# RainbowLED_2021_04_08_A.net
KiCad netlist of a schematic drawn in EAGLE
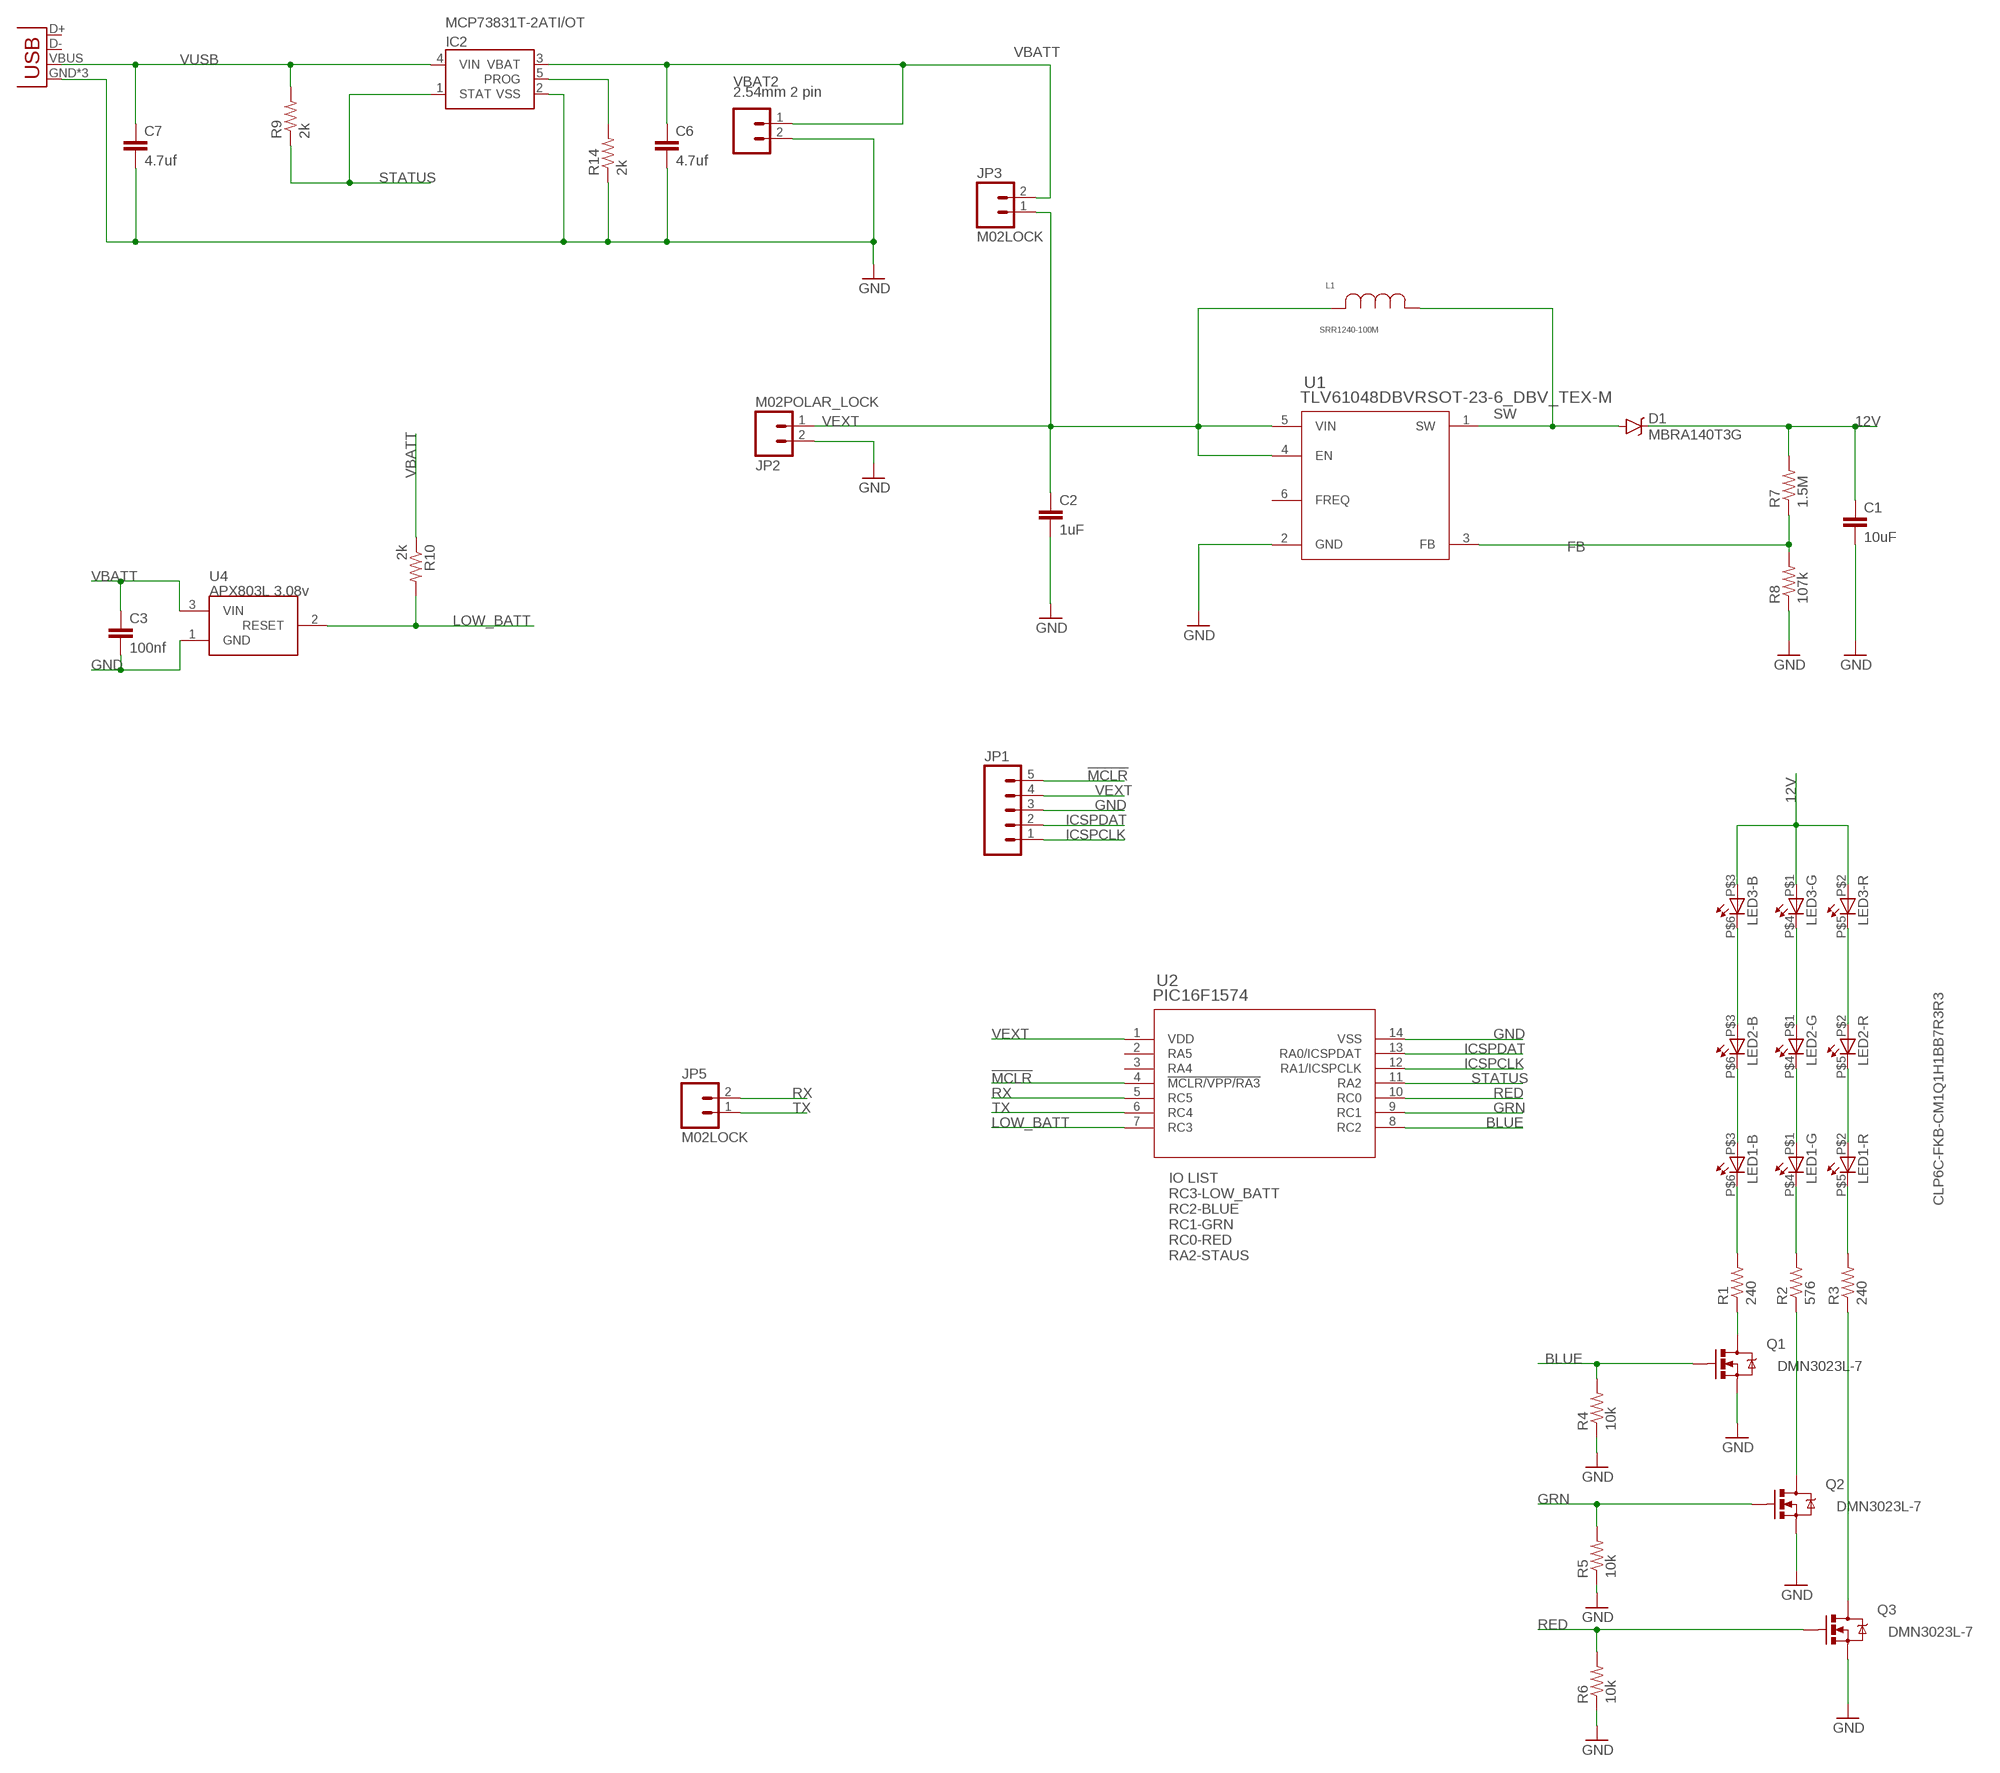
[diagram p0: schematic, sheet 1]

(export (version "E")
  (design (tool "Eeschema 10.0.6"))
  (components
    (comp (ref "C1")
      (value "10uF")
      (footprint "eagle-import:1206")
      (libsource (lib "eagle-import") (part "CAP1206"))
    )
    (comp (ref "C2")
      (value "1uF")
      (footprint "eagle-import:1206")
      (libsource (lib "eagle-import") (part "CAP1206"))
    )
    (comp (ref "C3")
      (value "100nf")
      (footprint "eagle-import:1206")
      (libsource (lib "eagle-import") (part "CAP1206"))
    )
    (comp (ref "C6")
      (value "4.7uf")
      (footprint "eagle-import:1206")
      (libsource (lib "eagle-import") (part "CAP1206"))
    )
    (comp (ref "C7")
      (value "4.7uf")
      (footprint "eagle-import:1206")
      (libsource (lib "eagle-import") (part "CAP1206"))
    )
    (comp (ref "D1")
      (value "MBRA140T3G")
      (footprint "eagle-import:SMA-DIODE")
      (libsource (lib "eagle-import") (part "DIODE-SCHOTTKY-MBRA140"))
    )
    (comp (ref "IC2")
      (value "MCP73831T-2ATI/OT")
      (footprint "eagle-import:SOT23-5")
      (libsource (lib "eagle-import") (part "MCP73831"))
    )
    (comp (ref "JP1")
      (value "M05LOCK")
      (footprint "eagle-import:1X05_LOCK")
      (libsource (lib "eagle-import") (part "M05LOCK"))
    )
    (comp (ref "JP2")
      (value "M02POLAR_LOCK")
      (footprint "eagle-import:MOLEX-1X2_LOCK")
      (libsource (lib "eagle-import") (part "M02POLAR_LOCK"))
    )
    (comp (ref "JP3")
      (value "M02LOCK")
      (footprint "eagle-import:1X02_LOCK")
      (libsource (lib "eagle-import") (part "M02LOCK"))
    )
    (comp (ref "JP4")
      (value "USB-MICROB")
      (footprint "eagle-import:USB-MICROB")
      (libsource (lib "eagle-import") (part "USB-MICROB"))
    )
    (comp (ref "JP5")
      (value "M02LOCK")
      (footprint "eagle-import:1X02_LOCK")
      (libsource (lib "eagle-import") (part "M02LOCK"))
    )
    (comp (ref "L1")
      (value "SRR1240-100M")
      (footprint "eagle-import:IND_BOURNS_SRR1240")
      (fields (field (name "MANUFACTURER_PART_NUMBER") "SRR1240100M"))
      (libsource (lib "eagle-import") (part "SRR1240-100M"))
    )
    (comp (ref "LED1")
      (value "CLX6F-FKC-CKNNQDGBB7A363")
      (footprint "eagle-import:PLCC-6")
      (libsource (lib "eagle-import") (part "OVSTRGBBCR8"))
    )
    (comp (ref "LED2")
      (value "CLX6F-FKC-CKNNQDGBB7A363")
      (footprint "eagle-import:PLCC-6")
      (libsource (lib "eagle-import") (part "OVSTRGBBCR8"))
    )
    (comp (ref "LED3")
      (value "CLX6F-FKC-CKNNQDGBB7A363")
      (footprint "eagle-import:PLCC-6")
      (libsource (lib "eagle-import") (part "OVSTRGBBCR8"))
    )
    (comp (ref "Q1")
      (value "DMN3023L-7")
      (footprint "eagle-import:SOT23-3")
      (libsource (lib "eagle-import") (part "MOSFET-NCHANNELBSS138"))
    )
    (comp (ref "Q2")
      (value "DMN3023L-7")
      (footprint "eagle-import:SOT23-3")
      (libsource (lib "eagle-import") (part "MOSFET-NCHANNELBSS138"))
    )
    (comp (ref "Q3")
      (value "DMN3023L-7")
      (footprint "eagle-import:SOT23-3")
      (libsource (lib "eagle-import") (part "MOSFET-NCHANNELBSS138"))
    )
    (comp (ref "R1")
      (value "240")
      (footprint "eagle-import:1206")
      (libsource (lib "eagle-import") (part "RESISTOR1206"))
    )
    (comp (ref "R2")
      (value "576")
      (footprint "eagle-import:1206")
      (libsource (lib "eagle-import") (part "RESISTOR1206"))
    )
    (comp (ref "R3")
      (value "240")
      (footprint "eagle-import:1206")
      (libsource (lib "eagle-import") (part "RESISTOR1206"))
    )
    (comp (ref "R4")
      (value "10k")
      (footprint "eagle-import:1206")
      (libsource (lib "eagle-import") (part "RESISTOR1206"))
    )
    (comp (ref "R5")
      (value "10k")
      (footprint "eagle-import:1206")
      (libsource (lib "eagle-import") (part "RESISTOR1206"))
    )
    (comp (ref "R6")
      (value "10k")
      (footprint "eagle-import:1206")
      (libsource (lib "eagle-import") (part "RESISTOR1206"))
    )
    (comp (ref "R7")
      (value "1.5M")
      (footprint "eagle-import:1206")
      (libsource (lib "eagle-import") (part "RESISTOR1206"))
    )
    (comp (ref "R8")
      (value "107k")
      (footprint "eagle-import:1206")
      (libsource (lib "eagle-import") (part "RESISTOR1206"))
    )
    (comp (ref "R9")
      (value "2k")
      (footprint "eagle-import:1206")
      (libsource (lib "eagle-import") (part "SparkFun-Resistors_RESISTOR1206"))
    )
    (comp (ref "R10")
      (value "2k")
      (footprint "eagle-import:1206")
      (libsource (lib "eagle-import") (part "SparkFun-Resistors_RESISTOR1206"))
    )
    (comp (ref "R14")
      (value "2k")
      (footprint "eagle-import:1206")
      (libsource (lib "eagle-import") (part "SparkFun-Resistors_RESISTOR1206"))
    )
    (comp (ref "U1")
      (value "TLV61048DBVRSOT-23-6_DBV_TEX-M")
      (footprint "eagle-import:SOT-23-6_DBV_TEX-M")
      (fields
        (field (name "MANUFACTURER_PART_NUMBER") "TLV61048DBVR")
        (field (name "COPYRIGHT") "Copyright (C) 2018 Accelerated Designs. All rights reserved")
      )
      (libsource (lib "eagle-import") (part "TLV61048DBVRSOT-23-6_DBV_TEX-M"))
    )
    (comp (ref "U2")
      (value "PIC16F1574")
      (footprint "eagle-import:SOIC14_SL")
      (fields (field (name "MANUFACTURER_PART_NUMBER") "PIC16F1503-I/SL"))
      (libsource (lib "eagle-import") (part "PIC16F1503-I/SL"))
    )
    (comp (ref "U4")
      (value "APX803L 3.08v")
      (footprint "eagle-import:SOT23")
      (libsource (lib "eagle-import") (part "ADP160"))
    )
    (comp (ref "VBAT2")
      (value "2.54mm 2 pin")
      (footprint "eagle-import:JST-2-PTH-VERT")
      (libsource (lib "eagle-import") (part "M02JST-PTH-VERT"))
    )
  )
  (nets
    (net (code "1") (name "/12V") (class "Default")
      (node (ref "C1") (pin "1") (pinfunction "1_1") (pintype "passive"))
      (node (ref "D1") (pin "C") (pinfunction "C_C") (pintype "passive"))
      (node (ref "LED3") (pin "P$1") (pinfunction "A_P$1") (pintype "passive"))
      (node (ref "LED3") (pin "P$2") (pinfunction "A_P$2") (pintype "passive"))
      (node (ref "LED3") (pin "P$3") (pinfunction "A_P$3") (pintype "passive"))
      (node (ref "R7") (pin "2") (pinfunction "2_2") (pintype "passive"))
    )
    (net (code "2") (name "/BLUE") (class "Default")
      (node (ref "Q1") (pin "1") (pinfunction "G_1") (pintype "passive"))
      (node (ref "R4") (pin "2") (pinfunction "2_2") (pintype "passive"))
      (node (ref "U2") (pin "8") (pinfunction "RC2_8") (pintype "bidirectional"))
    )
    (net (code "3") (name "/FB") (class "Default")
      (node (ref "R7") (pin "1") (pinfunction "1_1") (pintype "passive"))
      (node (ref "R8") (pin "2") (pinfunction "2_2") (pintype "passive"))
      (node (ref "U1") (pin "3") (pinfunction "FB_3") (pintype "input"))
    )
    (net (code "4") (name "/GRN") (class "Default")
      (node (ref "Q2") (pin "1") (pinfunction "G_1") (pintype "passive"))
      (node (ref "R5") (pin "2") (pinfunction "2_2") (pintype "passive"))
      (node (ref "U2") (pin "9") (pinfunction "RC1_9") (pintype "bidirectional"))
    )
    (net (code "5") (name "/ICSPCLK") (class "Default")
      (node (ref "JP1") (pin "1") (pinfunction "1_1") (pintype "passive"))
      (node (ref "U2") (pin "12") (pinfunction "RA1/ICSPCLK_12") (pintype "bidirectional"))
    )
    (net (code "6") (name "/ICSPDAT") (class "Default")
      (node (ref "JP1") (pin "2") (pinfunction "2_2") (pintype "passive"))
      (node (ref "U2") (pin "13") (pinfunction "RA0/ICSPDAT_13") (pintype "bidirectional"))
    )
    (net (code "7") (name "/LOW_BATT") (class "Default")
      (node (ref "R10") (pin "2") (pinfunction "2_2") (pintype "passive"))
      (node (ref "U2") (pin "7") (pinfunction "RC3_7") (pintype "bidirectional"))
      (node (ref "U4") (pin "2") (pinfunction "RESET_2") (pintype "bidirectional"))
    )
    (net (code "8") (name "/RED") (class "Default")
      (node (ref "Q3") (pin "1") (pinfunction "G_1") (pintype "passive"))
      (node (ref "R6") (pin "2") (pinfunction "2_2") (pintype "passive"))
      (node (ref "U2") (pin "10") (pinfunction "RC0_10") (pintype "bidirectional"))
    )
    (net (code "9") (name "/RX") (class "Default")
      (node (ref "JP5") (pin "2") (pinfunction "2_2") (pintype "passive"))
      (node (ref "U2") (pin "5") (pinfunction "RC5_5") (pintype "bidirectional"))
    )
    (net (code "10") (name "/STATUS") (class "Default")
      (node (ref "IC2") (pin "1") (pinfunction "STAT_1") (pintype "output"))
      (node (ref "R9") (pin "1") (pinfunction "1_1") (pintype "passive"))
      (node (ref "U2") (pin "11") (pinfunction "RA2_11") (pintype "bidirectional"))
    )
    (net (code "11") (name "/SW") (class "Default")
      (node (ref "D1") (pin "A") (pinfunction "A_A") (pintype "passive"))
      (node (ref "L1") (pin "1") (pinfunction "1_1") (pintype "passive"))
      (node (ref "U1") (pin "1") (pinfunction "SW_1") (pintype "power_in"))
    )
    (net (code "12") (name "/TX") (class "Default")
      (node (ref "JP5") (pin "1") (pinfunction "1_1") (pintype "passive"))
      (node (ref "U2") (pin "6") (pinfunction "RC4_6") (pintype "bidirectional"))
    )
    (net (code "13") (name "/VBATT") (class "Default")
      (node (ref "C3") (pin "1") (pinfunction "1_1") (pintype "passive"))
      (node (ref "C6") (pin "1") (pinfunction "1_1") (pintype "passive"))
      (node (ref "IC2") (pin "3") (pinfunction "VBAT_3") (pintype "power_in"))
      (node (ref "JP3") (pin "2") (pinfunction "2_2") (pintype "passive"))
      (node (ref "R10") (pin "1") (pinfunction "1_1") (pintype "passive"))
      (node (ref "U4") (pin "3") (pinfunction "VIN_3") (pintype "bidirectional"))
      (node (ref "VBAT2") (pin "1") (pinfunction "1_1") (pintype "passive"))
    )
    (net (code "14") (name "/VEXT") (class "Default")
      (node (ref "C2") (pin "1") (pinfunction "1_1") (pintype "passive"))
      (node (ref "JP1") (pin "4") (pinfunction "4_4") (pintype "passive"))
      (node (ref "JP2") (pin "1") (pinfunction "1_1") (pintype "passive"))
      (node (ref "JP3") (pin "1") (pinfunction "1_1") (pintype "passive"))
      (node (ref "L1") (pin "2") (pinfunction "2_2") (pintype "passive"))
      (node (ref "U1") (pin "4") (pinfunction "EN_4") (pintype "input"))
      (node (ref "U1") (pin "5") (pinfunction "VIN_5") (pintype "power_in"))
      (node (ref "U2") (pin "1") (pinfunction "VDD_1") (pintype "power_in"))
    )
    (net (code "15") (name "/VUSB") (class "Default")
      (node (ref "C7") (pin "1") (pinfunction "1_1") (pintype "passive"))
      (node (ref "IC2") (pin "4") (pinfunction "VIN_4") (pintype "power_in"))
      (node (ref "JP4") (pin "VBUS") (pinfunction "VBUS_VBUS") (pintype "bidirectional"))
      (node (ref "R9") (pin "2") (pinfunction "2_2") (pintype "passive"))
    )
    (net (code "16") (name "/~{MCLR}") (class "Default")
      (node (ref "JP1") (pin "5") (pinfunction "5_5") (pintype "passive"))
      (node (ref "U2") (pin "4") (pinfunction "~{MCLR/VPP/RA3}_4") (pintype "bidirectional"))
    )
    (net (code "17") (name "GND") (class "Default")
      (node (ref "C1") (pin "2") (pinfunction "2_2") (pintype "passive"))
      (node (ref "C2") (pin "2") (pinfunction "2_2") (pintype "passive"))
      (node (ref "C3") (pin "2") (pinfunction "2_2") (pintype "passive"))
      (node (ref "C6") (pin "2") (pinfunction "2_2") (pintype "passive"))
      (node (ref "C7") (pin "2") (pinfunction "2_2") (pintype "passive"))
      (node (ref "IC2") (pin "2") (pinfunction "VSS_2") (pintype "power_in"))
      (node (ref "JP1") (pin "3") (pinfunction "3_3") (pintype "passive"))
      (node (ref "JP2") (pin "2") (pinfunction "2_2") (pintype "passive"))
      (node (ref "JP4") (pin "GND") (pinfunction "GND_GND") (pintype "bidirectional"))
      (node (ref "JP4") (pin "MT1") (pinfunction "GND_MT1") (pintype "bidirectional"))
      (node (ref "JP4") (pin "MT2") (pinfunction "GND_MT2") (pintype "bidirectional"))
      (node (ref "Q1") (pin "2") (pinfunction "S_2") (pintype "passive"))
      (node (ref "Q2") (pin "2") (pinfunction "S_2") (pintype "passive"))
      (node (ref "Q3") (pin "2") (pinfunction "S_2") (pintype "passive"))
      (node (ref "R14") (pin "1") (pinfunction "1_1") (pintype "passive"))
      (node (ref "R4") (pin "1") (pinfunction "1_1") (pintype "passive"))
      (node (ref "R5") (pin "1") (pinfunction "1_1") (pintype "passive"))
      (node (ref "R6") (pin "1") (pinfunction "1_1") (pintype "passive"))
      (node (ref "R8") (pin "1") (pinfunction "1_1") (pintype "passive"))
      (node (ref "U1") (pin "2") (pinfunction "GND_2") (pintype "passive"))
      (node (ref "U2") (pin "14") (pinfunction "VSS_14") (pintype "power_in"))
      (node (ref "U4") (pin "1") (pinfunction "GND_1") (pintype "bidirectional"))
      (node (ref "VBAT2") (pin "2") (pinfunction "2_2") (pintype "passive"))
    )
    (net (code "18") (name "Net-(IC2-PROG)") (class "Default")
      (node (ref "IC2") (pin "5") (pinfunction "PROG_5") (pintype "input"))
      (node (ref "R14") (pin "2") (pinfunction "2_2") (pintype "passive"))
    )
    (net (code "19") (name "Net-(LED1A-A)") (class "Default")
      (node (ref "LED1") (pin "P$3") (pinfunction "A_P$3") (pintype "passive"))
      (node (ref "LED2") (pin "P$6") (pinfunction "C_P$6") (pintype "passive"))
    )
    (net (code "20") (name "Net-(LED1A-C)") (class "Default")
      (node (ref "LED1") (pin "P$6") (pinfunction "C_P$6") (pintype "passive"))
      (node (ref "R1") (pin "2") (pinfunction "2_2") (pintype "passive"))
    )
    (net (code "21") (name "Net-(LED1B-A)") (class "Default")
      (node (ref "LED1") (pin "P$1") (pinfunction "A_P$1") (pintype "passive"))
      (node (ref "LED2") (pin "P$4") (pinfunction "C_P$4") (pintype "passive"))
    )
    (net (code "22") (name "Net-(LED1B-C)") (class "Default")
      (node (ref "LED1") (pin "P$4") (pinfunction "C_P$4") (pintype "passive"))
      (node (ref "R2") (pin "2") (pinfunction "2_2") (pintype "passive"))
    )
    (net (code "23") (name "Net-(LED1C-A)") (class "Default")
      (node (ref "LED1") (pin "P$2") (pinfunction "A_P$2") (pintype "passive"))
      (node (ref "LED2") (pin "P$5") (pinfunction "C_P$5") (pintype "passive"))
    )
    (net (code "24") (name "Net-(LED1C-C)") (class "Default")
      (node (ref "LED1") (pin "P$5") (pinfunction "C_P$5") (pintype "passive"))
      (node (ref "R3") (pin "2") (pinfunction "2_2") (pintype "passive"))
    )
    (net (code "25") (name "Net-(LED2A-A)") (class "Default")
      (node (ref "LED2") (pin "P$3") (pinfunction "A_P$3") (pintype "passive"))
      (node (ref "LED3") (pin "P$6") (pinfunction "C_P$6") (pintype "passive"))
    )
    (net (code "26") (name "Net-(LED2B-A)") (class "Default")
      (node (ref "LED2") (pin "P$1") (pinfunction "A_P$1") (pintype "passive"))
      (node (ref "LED3") (pin "P$4") (pinfunction "C_P$4") (pintype "passive"))
    )
    (net (code "27") (name "Net-(LED2C-A)") (class "Default")
      (node (ref "LED2") (pin "P$2") (pinfunction "A_P$2") (pintype "passive"))
      (node (ref "LED3") (pin "P$5") (pinfunction "C_P$5") (pintype "passive"))
    )
    (net (code "28") (name "Net-(Q1-D)") (class "Default")
      (node (ref "Q1") (pin "3") (pinfunction "D_3") (pintype "passive"))
      (node (ref "R1") (pin "1") (pinfunction "1_1") (pintype "passive"))
    )
    (net (code "29") (name "Net-(Q2-D)") (class "Default")
      (node (ref "Q2") (pin "3") (pinfunction "D_3") (pintype "passive"))
      (node (ref "R2") (pin "1") (pinfunction "1_1") (pintype "passive"))
    )
    (net (code "30") (name "Net-(Q3-D)") (class "Default")
      (node (ref "Q3") (pin "3") (pinfunction "D_3") (pintype "passive"))
      (node (ref "R3") (pin "1") (pinfunction "1_1") (pintype "passive"))
    )
    (net (code "31") (name "unconnected-(JP4-PadD+)") (class "Default")
      (node (ref "JP4") (pin "D+") (pinfunction "D+_D+") (pintype "bidirectional"))
    )
    (net (code "32") (name "unconnected-(JP4-PadD-)") (class "Default")
      (node (ref "JP4") (pin "D-") (pinfunction "D-_D-") (pintype "bidirectional"))
    )
    (net (code "33") (name "unconnected-(U1-FREQ-Pad6)") (class "Default")
      (node (ref "U1") (pin "6") (pinfunction "FREQ_6") (pintype "input"))
    )
    (net (code "34") (name "unconnected-(U2-RA4-Pad3)") (class "Default")
      (node (ref "U2") (pin "3") (pinfunction "RA4_3") (pintype "bidirectional"))
    )
    (net (code "35") (name "unconnected-(U2-RA5-Pad2)") (class "Default")
      (node (ref "U2") (pin "2") (pinfunction "RA5_2") (pintype "bidirectional"))
    )
  )
)
